# WheeStatX-7.net
KiCad netlist of a schematic drawn in EAGLE
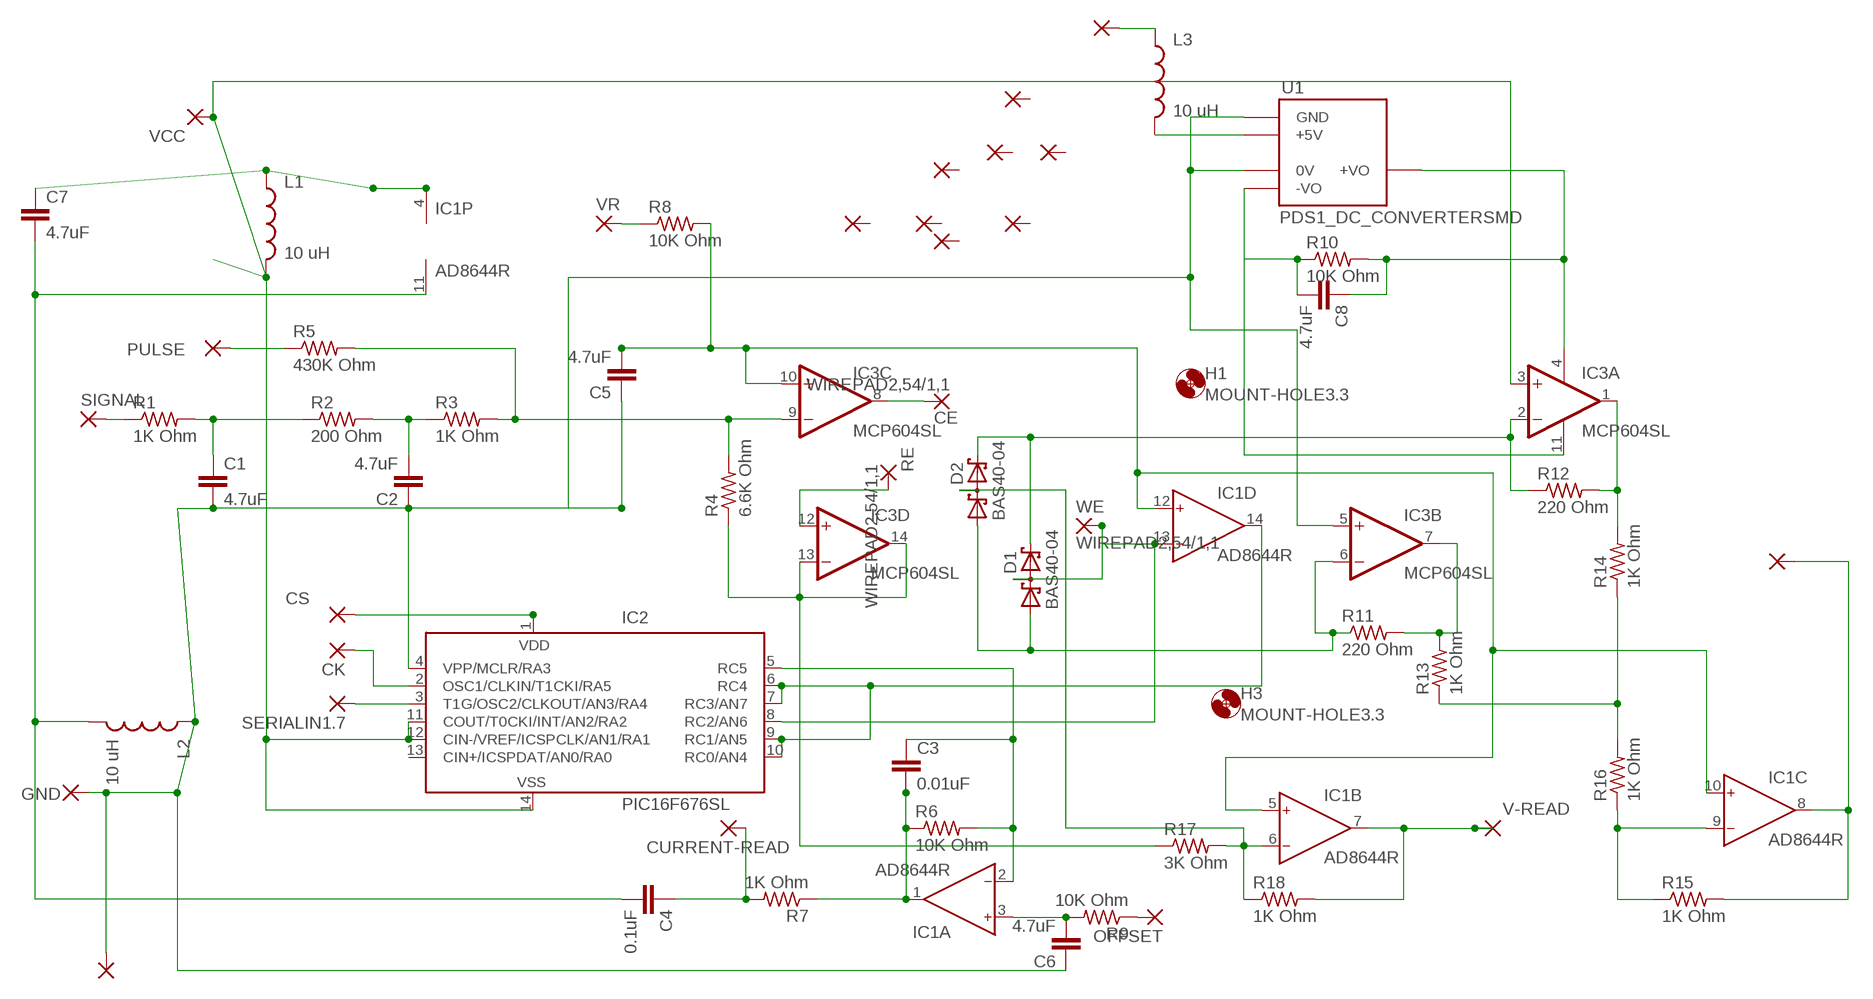
[diagram p0: schematic, sheet 1]

(export (version "E")
  (design (tool "Eeschema 10.0.6"))
  (components
    (comp (ref "1")
      (value "1,6/0,9")
      (footprint "eagle-import:1,6_0,9")
      (libsource (lib "eagle-import") (part "1,6/0,9"))
    )
    (comp (ref "1.1")
      (value "1,6/0,9")
      (footprint "eagle-import:1,6_0,9")
      (libsource (lib "eagle-import") (part "1,6/0,9"))
    )
    (comp (ref "1.4")
      (value "1,6/0,9")
      (footprint "eagle-import:1,6_0,9")
      (libsource (lib "eagle-import") (part "1,6/0,9"))
    )
    (comp (ref "2")
      (value "1,6/0,9")
      (footprint "eagle-import:1,6_0,9")
      (libsource (lib "eagle-import") (part "1,6/0,9"))
    )
    (comp (ref "3")
      (value "1,6/0,9")
      (footprint "eagle-import:1,6_0,9")
      (libsource (lib "eagle-import") (part "1,6/0,9"))
    )
    (comp (ref "4")
      (value "1,6/0,9")
      (footprint "eagle-import:1,6_0,9")
      (libsource (lib "eagle-import") (part "1,6/0,9"))
    )
    (comp (ref "5")
      (value "1,6/0,9")
      (footprint "eagle-import:1,6_0,9")
      (libsource (lib "eagle-import") (part "1,6/0,9"))
    )
    (comp (ref "6")
      (value "1,6/0,9")
      (footprint "eagle-import:1,6_0,9")
      (libsource (lib "eagle-import") (part "1,6/0,9"))
    )
    (comp (ref "7")
      (value "1,6/0,9")
      (footprint "eagle-import:1,6_0,9")
      (libsource (lib "eagle-import") (part "1,6/0,9"))
    )
    (comp (ref "9")
      (value "1,6/0,9")
      (footprint "eagle-import:1,6_0,9")
      (libsource (lib "eagle-import") (part "1,6/0,9"))
    )
    (comp (ref "10")
      (value "1,6/0,9")
      (footprint "eagle-import:1,6_0,9")
      (libsource (lib "eagle-import") (part "1,6/0,9"))
    )
    (comp (ref "C1")
      (value "4.7uF")
      (footprint "eagle-import:C0603")
      (libsource (lib "eagle-import") (part "resistor_C-EUC0603"))
    )
    (comp (ref "C2")
      (value "4.7uF")
      (footprint "eagle-import:C0603")
      (libsource (lib "eagle-import") (part "resistor_C-EUC0603"))
    )
    (comp (ref "C3")
      (value "0.01uF")
      (footprint "eagle-import:C0603")
      (libsource (lib "eagle-import") (part "resistor_C-EUC0603"))
    )
    (comp (ref "C4")
      (value "0.1uF")
      (footprint "eagle-import:C0603")
      (libsource (lib "eagle-import") (part "resistor_C-EUC0603"))
    )
    (comp (ref "C5")
      (value "4.7uF")
      (footprint "eagle-import:C0603")
      (libsource (lib "eagle-import") (part "resistor_C-EUC0603"))
    )
    (comp (ref "C6")
      (value "4.7uF")
      (footprint "eagle-import:C0603")
      (libsource (lib "eagle-import") (part "resistor_C-EUC0603"))
    )
    (comp (ref "C7")
      (value "4.7uF")
      (footprint "eagle-import:C0603@1")
      (libsource (lib "eagle-import") (part "C-EUC0603"))
    )
    (comp (ref "C8")
      (value "4.7uF")
      (footprint "eagle-import:C0603")
      (libsource (lib "eagle-import") (part "resistor_C-EUC0603"))
    )
    (comp (ref "CE")
      (value "WIREPAD2,54/1,1")
      (footprint "eagle-import:2,54_1,1")
      (libsource (lib "eagle-import") (part "WIREPAD2,54/1,1"))
    )
    (comp (ref "CK")
      (value "1,6/0,9")
      (footprint "eagle-import:1,6_0,9")
      (libsource (lib "eagle-import") (part "1,6/0,9"))
    )
    (comp (ref "CS")
      (value "1,6/0,9")
      (footprint "eagle-import:1,6_0,9")
      (libsource (lib "eagle-import") (part "1,6/0,9"))
    )
    (comp (ref "CURRENT-READ")
      (value "1,6/0,9")
      (footprint "eagle-import:1,6_0,9")
      (libsource (lib "eagle-import") (part "1,6/0,9"))
    )
    (comp (ref "D1")
      (value "BAS40-04")
      (footprint "eagle-import:SOT23")
      (libsource (lib "eagle-import") (part "BAS40-04"))
    )
    (comp (ref "D2")
      (value "BAS40-04")
      (footprint "eagle-import:SOT23")
      (libsource (lib "eagle-import") (part "BAS40-04"))
    )
    (comp (ref "GND")
      (value "1,6/0,9")
      (footprint "eagle-import:1,6_0,9")
      (libsource (lib "eagle-import") (part "1,6/0,9"))
    )
    (comp (ref "H1")
      (value "MOUNT-HOLE3.3")
      (footprint "eagle-import:3,3")
      (libsource (lib "eagle-import") (part "MOUNT-HOLE3.3"))
    )
    (comp (ref "H3")
      (value "MOUNT-HOLE3.3")
      (footprint "eagle-import:3,3")
      (libsource (lib "eagle-import") (part "MOUNT-HOLE3.3"))
    )
    (comp (ref "IC1")
      (value "AD8644R")
      (footprint "eagle-import:SO14")
      (fields (field (name "MF") "ALTERA CORPORATION") (field (name "MPN") "AD8644ARZ"))
      (libsource (lib "eagle-import") (part "AD8644R"))
    )
    (comp (ref "IC2")
      (value "PIC16F676SL")
      (footprint "eagle-import:SO-14")
      (fields (field (name "MF") "MICROCHIP") (field (name "MPN") "PIC16F676-I/SL"))
      (libsource (lib "eagle-import") (part "PIC16F676SL"))
    )
    (comp (ref "IC3")
      (value "MCP604SL")
      (footprint "eagle-import:SO14")
      (libsource (lib "eagle-import") (part "MCP604SL"))
    )
    (comp (ref "L1")
      (value "10 uH")
      (footprint "eagle-import:0603")
      (libsource (lib "eagle-import") (part "INDUCTOR0603"))
    )
    (comp (ref "L2")
      (value "10 uH")
      (footprint "eagle-import:0603")
      (libsource (lib "eagle-import") (part "INDUCTOR0603"))
    )
    (comp (ref "L3")
      (value "10 uH")
      (footprint "eagle-import:0603")
      (libsource (lib "eagle-import") (part "INDUCTOR0603"))
    )
    (comp (ref "OFFSET")
      (value "1,6/0,9")
      (footprint "eagle-import:1,6_0,9")
      (libsource (lib "eagle-import") (part "1,6/0,9"))
    )
    (comp (ref "PULSE")
      (value "1,6/0,9")
      (footprint "eagle-import:1,6_0,9")
      (libsource (lib "eagle-import") (part "1,6/0,9"))
    )
    (comp (ref "R1")
      (value "1K Ohm")
      (footprint "eagle-import:R0603")
      (libsource (lib "eagle-import") (part "R-US_R0603"))
    )
    (comp (ref "R2")
      (value "200 Ohm")
      (footprint "eagle-import:R0603")
      (libsource (lib "eagle-import") (part "R-US_R0603"))
    )
    (comp (ref "R3")
      (value "1K Ohm")
      (footprint "eagle-import:R0603")
      (libsource (lib "eagle-import") (part "R-US_R0603"))
    )
    (comp (ref "R4")
      (value "6.6K Ohm")
      (footprint "eagle-import:R0603")
      (libsource (lib "eagle-import") (part "R-US_R0603"))
    )
    (comp (ref "R5")
      (value "430K Ohm")
      (footprint "eagle-import:R0603")
      (libsource (lib "eagle-import") (part "R-US_R0603"))
    )
    (comp (ref "R6")
      (value "10K Ohm")
      (footprint "eagle-import:R0603")
      (libsource (lib "eagle-import") (part "R-US_R0603"))
    )
    (comp (ref "R7")
      (value "1K Ohm")
      (footprint "eagle-import:R0603")
      (libsource (lib "eagle-import") (part "R-US_R0603"))
    )
    (comp (ref "R8")
      (value "10K Ohm")
      (footprint "eagle-import:R0603")
      (libsource (lib "eagle-import") (part "R-US_R0603"))
    )
    (comp (ref "R9")
      (value "10K Ohm")
      (footprint "eagle-import:R0603")
      (libsource (lib "eagle-import") (part "R-US_R0603"))
    )
    (comp (ref "R10")
      (value "10K Ohm")
      (footprint "eagle-import:R0603")
      (libsource (lib "eagle-import") (part "R-US_R0603"))
    )
    (comp (ref "R11")
      (value "220 Ohm")
      (footprint "eagle-import:R0603")
      (libsource (lib "eagle-import") (part "R-US_R0603"))
    )
    (comp (ref "R12")
      (value "220 Ohm")
      (footprint "eagle-import:R0603")
      (libsource (lib "eagle-import") (part "R-US_R0603"))
    )
    (comp (ref "R13")
      (value "1K Ohm")
      (footprint "eagle-import:R0603")
      (libsource (lib "eagle-import") (part "R-US_R0603"))
    )
    (comp (ref "R14")
      (value "1K Ohm")
      (footprint "eagle-import:R0603")
      (libsource (lib "eagle-import") (part "R-US_R0603"))
    )
    (comp (ref "R15")
      (value "1K Ohm")
      (footprint "eagle-import:R0603")
      (libsource (lib "eagle-import") (part "R-US_R0603"))
    )
    (comp (ref "R16")
      (value "1K Ohm")
      (footprint "eagle-import:R0603")
      (libsource (lib "eagle-import") (part "R-US_R0603"))
    )
    (comp (ref "R17")
      (value "3K Ohm")
      (footprint "eagle-import:R0603")
      (libsource (lib "eagle-import") (part "R-US_R0603"))
    )
    (comp (ref "R18")
      (value "1K Ohm")
      (footprint "eagle-import:R0603")
      (libsource (lib "eagle-import") (part "R-US_R0603"))
    )
    (comp (ref "RE")
      (value "WIREPAD2,54/1,1")
      (footprint "eagle-import:2,54_1,1")
      (libsource (lib "eagle-import") (part "WIREPAD2,54/1,1"))
    )
    (comp (ref "SERIALIN1.7")
      (value "1,6/0,9")
      (footprint "eagle-import:1,6_0,9")
      (libsource (lib "eagle-import") (part "1,6/0,9"))
    )
    (comp (ref "SIGNAL")
      (value "1,6/0,9")
      (footprint "eagle-import:1,6_0,9")
      (libsource (lib "eagle-import") (part "1,6/0,9"))
    )
    (comp (ref "U1")
      (value "PDS1_DC_CONVERTERSMD")
      (footprint "eagle-import:PDS1")
      (libsource (lib "eagle-import") (part "PDS1_DC_CONVERTERSMD"))
    )
    (comp (ref "V-READ")
      (value "1,6/0,9")
      (footprint "eagle-import:1,6_0,9")
      (libsource (lib "eagle-import") (part "1,6/0,9"))
    )
    (comp (ref "VCC")
      (value "1,6/0,9")
      (footprint "eagle-import:1,6_0,9")
      (libsource (lib "eagle-import") (part "1,6/0,9"))
    )
    (comp (ref "VR")
      (value "1,6/0,9")
      (footprint "eagle-import:1,6_0,9")
      (libsource (lib "eagle-import") (part "1,6/0,9"))
    )
    (comp (ref "WE")
      (value "WIREPAD2,54/1,1")
      (footprint "eagle-import:2,54_1,1")
      (libsource (lib "eagle-import") (part "WIREPAD2,54/1,1"))
    )
  )
  (nets
    (net (code "1") (name "Net-(1.1-P)") (class "Default")
      (node (ref "1.1") (pin "1") (pinfunction "P_1") (pintype "passive"))
      (node (ref "C1") (pin "2") (pinfunction "2_2") (pintype "passive"))
      (node (ref "C2") (pin "1") (pinfunction "1_1") (pintype "passive"))
      (node (ref "C5") (pin "1") (pinfunction "1_1") (pintype "passive"))
      (node (ref "C6") (pin "1") (pinfunction "1_1") (pintype "passive"))
      (node (ref "GND") (pin "1") (pinfunction "P_1") (pintype "passive"))
      (node (ref "IC2") (pin "4") (pinfunction "VPP/MCLR/RA3_4") (pintype "input"))
      (node (ref "IC3") (pin "5") (pinfunction "+IN_5") (pintype "input"))
      (node (ref "L2") (pin "1") (pinfunction "1_1") (pintype "passive"))
      (node (ref "U1") (pin "1") (pinfunction "GND_1") (pintype "power_in"))
      (node (ref "U1") (pin "4") (pinfunction "0V_4") (pintype "power_in"))
    )
    (net (code "2") (name "Net-(1.4-P)") (class "Default")
      (node (ref "1.4") (pin "1") (pinfunction "P_1") (pintype "passive"))
      (node (ref "IC1") (pin "8") (pinfunction "OUT_8") (pintype "output"))
      (node (ref "R15") (pin "2") (pinfunction "2_2") (pintype "passive"))
    )
    (net (code "3") (name "Net-(9-P)") (class "Default")
      (node (ref "9") (pin "1") (pinfunction "P_1") (pintype "passive"))
      (node (ref "L3") (pin "1") (pinfunction "1_1") (pintype "passive"))
    )
    (net (code "4") (name "Net-(C1-Pad1)") (class "Default")
      (node (ref "C1") (pin "1") (pinfunction "1_1") (pintype "passive"))
      (node (ref "R1") (pin "2") (pinfunction "2_2") (pintype "passive"))
      (node (ref "R2") (pin "1") (pinfunction "1_1") (pintype "passive"))
    )
    (net (code "5") (name "Net-(C2-Pad2)") (class "Default")
      (node (ref "C2") (pin "2") (pinfunction "2_2") (pintype "passive"))
      (node (ref "R2") (pin "2") (pinfunction "2_2") (pintype "passive"))
      (node (ref "R3") (pin "1") (pinfunction "1_1") (pintype "passive"))
    )
    (net (code "6") (name "Net-(CE-P)") (class "Default")
      (node (ref "CE") (pin "1") (pinfunction "P_1") (pintype "passive"))
      (node (ref "IC3") (pin "8") (pinfunction "OUT_8") (pintype "output"))
    )
    (net (code "7") (name "Net-(CK-P)") (class "Default")
      (node (ref "CK") (pin "1") (pinfunction "P_1") (pintype "passive"))
      (node (ref "IC2") (pin "2") (pinfunction "OSC1/CLKIN/T1CKI/RA5_2") (pintype "bidirectional"))
    )
    (net (code "8") (name "Net-(CS-P)") (class "Default")
      (node (ref "CS") (pin "1") (pinfunction "P_1") (pintype "passive"))
      (node (ref "IC2") (pin "1") (pinfunction "VDD_1") (pintype "power_in"))
    )
    (net (code "9") (name "Net-(CURRENT-READ-P)") (class "Default")
      (node (ref "C4") (pin "1") (pinfunction "1_1") (pintype "passive"))
      (node (ref "CURRENT-READ") (pin "1") (pinfunction "P_1") (pintype "passive"))
      (node (ref "R7") (pin "2") (pinfunction "2_2") (pintype "passive"))
    )
    (net (code "10") (name "Net-(D1-A1)") (class "Default")
      (node (ref "D1") (pin "1") (pinfunction "A1_1") (pintype "passive"))
      (node (ref "D2") (pin "1") (pinfunction "A1_1") (pintype "passive"))
      (node (ref "IC3") (pin "6") (pinfunction "-IN_6") (pintype "input"))
      (node (ref "R11") (pin "1") (pinfunction "1_1") (pintype "passive"))
    )
    (net (code "11") (name "Net-(D1-C1A2)") (class "Default")
      (node (ref "D1") (pin "3") (pinfunction "C1A2_3") (pintype "passive"))
      (node (ref "IC1") (pin "13") (pinfunction "IN-_13") (pintype "input"))
      (node (ref "IC2") (pin "8") (pinfunction "RC2/AN6_8") (pintype "bidirectional"))
      (node (ref "WE") (pin "1") (pinfunction "P_1") (pintype "passive"))
    )
    (net (code "12") (name "Net-(D1-C2)") (class "Default")
      (node (ref "D1") (pin "2") (pinfunction "C2_2") (pintype "passive"))
      (node (ref "D2") (pin "2") (pinfunction "C2_2") (pintype "passive"))
      (node (ref "IC3") (pin "2") (pinfunction "-IN_2") (pintype "input"))
      (node (ref "R12") (pin "1") (pinfunction "1_1") (pintype "passive"))
    )
    (net (code "13") (name "Net-(D2-C1A2)") (class "Default")
      (node (ref "D2") (pin "3") (pinfunction "C1A2_3") (pintype "passive"))
      (node (ref "IC1") (pin "6") (pinfunction "IN-_6") (pintype "input"))
      (node (ref "R17") (pin "2") (pinfunction "2_2") (pintype "passive"))
      (node (ref "R18") (pin "1") (pinfunction "1_1") (pintype "passive"))
    )
    (net (code "14") (name "Net-(IC1A-IN+)") (class "Default")
      (node (ref "C6") (pin "2") (pinfunction "2_2") (pintype "passive"))
      (node (ref "IC1") (pin "3") (pinfunction "IN+_3") (pintype "input"))
      (node (ref "R9") (pin "2") (pinfunction "2_2") (pintype "passive"))
    )
    (net (code "15") (name "Net-(IC1A-IN-)") (class "Default")
      (node (ref "C3") (pin "1") (pinfunction "1_1") (pintype "passive"))
      (node (ref "IC1") (pin "2") (pinfunction "IN-_2") (pintype "input"))
      (node (ref "IC2") (pin "5") (pinfunction "RC5_5") (pintype "bidirectional"))
      (node (ref "R6") (pin "2") (pinfunction "2_2") (pintype "passive"))
    )
    (net (code "16") (name "Net-(IC1A-OUT)") (class "Default")
      (node (ref "C3") (pin "2") (pinfunction "2_2") (pintype "passive"))
      (node (ref "IC1") (pin "1") (pinfunction "OUT_1") (pintype "output"))
      (node (ref "R6") (pin "1") (pinfunction "1_1") (pintype "passive"))
      (node (ref "R7") (pin "1") (pinfunction "1_1") (pintype "passive"))
    )
    (net (code "17") (name "Net-(IC1B-IN+)") (class "Default")
      (node (ref "C5") (pin "2") (pinfunction "2_2") (pintype "passive"))
      (node (ref "IC1") (pin "10") (pinfunction "IN+_10") (pintype "input"))
      (node (ref "IC1") (pin "12") (pinfunction "IN+_12") (pintype "input"))
      (node (ref "IC1") (pin "5") (pinfunction "IN+_5") (pintype "input"))
      (node (ref "IC3") (pin "10") (pinfunction "+IN_10") (pintype "input"))
      (node (ref "R8") (pin "2") (pinfunction "2_2") (pintype "passive"))
    )
    (net (code "18") (name "Net-(IC1B-OUT)") (class "Default")
      (node (ref "IC1") (pin "7") (pinfunction "OUT_7") (pintype "output"))
      (node (ref "R18") (pin "2") (pinfunction "2_2") (pintype "passive"))
      (node (ref "V-READ") (pin "1") (pinfunction "P_1") (pintype "passive"))
    )
    (net (code "19") (name "Net-(IC1C-IN-)") (class "Default")
      (node (ref "IC1") (pin "9") (pinfunction "IN-_9") (pintype "input"))
      (node (ref "R15") (pin "1") (pinfunction "1_1") (pintype "passive"))
      (node (ref "R16") (pin "1") (pinfunction "1_1") (pintype "passive"))
    )
    (net (code "20") (name "Net-(IC1D-OUT)") (class "Default")
      (node (ref "IC1") (pin "14") (pinfunction "OUT_14") (pintype "output"))
      (node (ref "IC2") (pin "10") (pinfunction "RC0/AN4_10") (pintype "bidirectional"))
      (node (ref "IC2") (pin "6") (pinfunction "RC4_6") (pintype "bidirectional"))
      (node (ref "IC2") (pin "7") (pinfunction "RC3/AN7_7") (pintype "bidirectional"))
      (node (ref "IC2") (pin "9") (pinfunction "RC1/AN5_9") (pintype "bidirectional"))
    )
    (net (code "21") (name "Net-(IC1E-V+)") (class "Default")
      (node (ref "C7") (pin "1") (pinfunction "1_1") (pintype "passive"))
      (node (ref "IC1") (pin "4") (pinfunction "V+_4") (pintype "power_in"))
      (node (ref "L1") (pin "1") (pinfunction "1_1") (pintype "passive"))
    )
    (net (code "22") (name "Net-(IC1E-V-)") (class "Default")
      (node (ref "C4") (pin "2") (pinfunction "2_2") (pintype "passive"))
      (node (ref "C7") (pin "2") (pinfunction "2_2") (pintype "passive"))
      (node (ref "IC1") (pin "11") (pinfunction "V-_11") (pintype "power_in"))
      (node (ref "L2") (pin "2") (pinfunction "2_2") (pintype "passive"))
    )
    (net (code "23") (name "Net-(IC2-CIN-{slash}VREF{slash}ICSPCLK{slash}AN1{slash}RA1)") (class "Default")
      (node (ref "IC2") (pin "11") (pinfunction "COUT/T0CKI/INT/AN2/RA2_11") (pintype "bidirectional"))
      (node (ref "IC2") (pin "12") (pinfunction "CIN-/VREF/ICSPCLK/AN1/RA1_12") (pintype "bidirectional"))
      (node (ref "IC2") (pin "14") (pinfunction "VSS_14") (pintype "power_in"))
      (node (ref "IC3") (pin "3") (pinfunction "+IN_3") (pintype "input"))
      (node (ref "L1") (pin "2") (pinfunction "2_2") (pintype "passive"))
      (node (ref "VCC") (pin "1") (pinfunction "P_1") (pintype "passive"))
    )
    (net (code "24") (name "Net-(IC2-T1G{slash}OSC2{slash}CLKOUT{slash}AN3{slash}RA4)") (class "Default")
      (node (ref "IC2") (pin "3") (pinfunction "T1G/OSC2/CLKOUT/AN3/RA4_3") (pintype "bidirectional"))
      (node (ref "SERIALIN1.7") (pin "1") (pinfunction "P_1") (pintype "passive"))
    )
    (net (code "25") (name "Net-(IC3A-OUT)") (class "Default")
      (node (ref "IC3") (pin "1") (pinfunction "OUT_1") (pintype "output"))
      (node (ref "R12") (pin "2") (pinfunction "2_2") (pintype "passive"))
      (node (ref "R14") (pin "2") (pinfunction "2_2") (pintype "passive"))
    )
    (net (code "26") (name "Net-(IC3B-OUT)") (class "Default")
      (node (ref "IC3") (pin "7") (pinfunction "OUT_7") (pintype "output"))
      (node (ref "R11") (pin "2") (pinfunction "2_2") (pintype "passive"))
      (node (ref "R13") (pin "2") (pinfunction "2_2") (pintype "passive"))
    )
    (net (code "27") (name "Net-(IC3C--IN)") (class "Default")
      (node (ref "IC3") (pin "9") (pinfunction "-IN_9") (pintype "input"))
      (node (ref "R3") (pin "2") (pinfunction "2_2") (pintype "passive"))
      (node (ref "R4") (pin "2") (pinfunction "2_2") (pintype "passive"))
      (node (ref "R5") (pin "2") (pinfunction "2_2") (pintype "passive"))
    )
    (net (code "28") (name "Net-(IC3D-+IN)") (class "Default")
      (node (ref "IC3") (pin "12") (pinfunction "+IN_12") (pintype "input"))
      (node (ref "RE") (pin "1") (pinfunction "P_1") (pintype "passive"))
    )
    (net (code "29") (name "Net-(IC3D--IN)") (class "Default")
      (node (ref "IC3") (pin "13") (pinfunction "-IN_13") (pintype "input"))
      (node (ref "IC3") (pin "14") (pinfunction "OUT_14") (pintype "output"))
      (node (ref "R17") (pin "1") (pinfunction "1_1") (pintype "passive"))
      (node (ref "R4") (pin "1") (pinfunction "1_1") (pintype "passive"))
    )
    (net (code "30") (name "Net-(IC3E-V+)") (class "Default")
      (node (ref "C8") (pin "1") (pinfunction "1_1") (pintype "passive"))
      (node (ref "IC3") (pin "4") (pinfunction "V+_4") (pintype "power_in"))
      (node (ref "R10") (pin "2") (pinfunction "2_2") (pintype "passive"))
      (node (ref "U1") (pin "7") (pinfunction "+VO_7") (pintype "power_in"))
    )
    (net (code "31") (name "Net-(IC3E-V-)") (class "Default")
      (node (ref "C8") (pin "2") (pinfunction "2_2") (pintype "passive"))
      (node (ref "IC3") (pin "11") (pinfunction "V-_11") (pintype "power_in"))
      (node (ref "R10") (pin "1") (pinfunction "1_1") (pintype "passive"))
      (node (ref "U1") (pin "5") (pinfunction "-VO_5") (pintype "power_in"))
    )
    (net (code "32") (name "Net-(OFFSET-P)") (class "Default")
      (node (ref "OFFSET") (pin "1") (pinfunction "P_1") (pintype "passive"))
      (node (ref "R9") (pin "1") (pinfunction "1_1") (pintype "passive"))
    )
    (net (code "33") (name "Net-(PULSE-P)") (class "Default")
      (node (ref "PULSE") (pin "1") (pinfunction "P_1") (pintype "passive"))
      (node (ref "R5") (pin "1") (pinfunction "1_1") (pintype "passive"))
    )
    (net (code "34") (name "Net-(R13-Pad1)") (class "Default")
      (node (ref "R13") (pin "1") (pinfunction "1_1") (pintype "passive"))
      (node (ref "R14") (pin "1") (pinfunction "1_1") (pintype "passive"))
      (node (ref "R16") (pin "2") (pinfunction "2_2") (pintype "passive"))
    )
    (net (code "35") (name "Net-(SIGNAL-P)") (class "Default")
      (node (ref "R1") (pin "1") (pinfunction "1_1") (pintype "passive"))
      (node (ref "SIGNAL") (pin "1") (pinfunction "P_1") (pintype "passive"))
    )
    (net (code "36") (name "Net-(U1-+5V)") (class "Default")
      (node (ref "L3") (pin "2") (pinfunction "2_2") (pintype "passive"))
      (node (ref "U1") (pin "2") (pinfunction "+5V_2") (pintype "power_in"))
    )
    (net (code "37") (name "Net-(VR-P)") (class "Default")
      (node (ref "R8") (pin "1") (pinfunction "1_1") (pintype "passive"))
      (node (ref "VR") (pin "1") (pinfunction "P_1") (pintype "passive"))
    )
    (net (code "38") (name "unconnected-(1-P-Pad1)") (class "Default")
      (node (ref "1") (pin "1") (pinfunction "P_1") (pintype "passive"))
    )
    (net (code "39") (name "unconnected-(2-P-Pad1)") (class "Default")
      (node (ref "2") (pin "1") (pinfunction "P_1") (pintype "passive"))
    )
    (net (code "40") (name "unconnected-(3-P-Pad1)") (class "Default")
      (node (ref "3") (pin "1") (pinfunction "P_1") (pintype "passive"))
    )
    (net (code "41") (name "unconnected-(4-P-Pad1)") (class "Default")
      (node (ref "4") (pin "1") (pinfunction "P_1") (pintype "passive"))
    )
    (net (code "42") (name "unconnected-(5-P-Pad1)") (class "Default")
      (node (ref "5") (pin "1") (pinfunction "P_1") (pintype "passive"))
    )
    (net (code "43") (name "unconnected-(6-P-Pad1)") (class "Default")
      (node (ref "6") (pin "1") (pinfunction "P_1") (pintype "passive"))
    )
    (net (code "44") (name "unconnected-(7-P-Pad1)") (class "Default")
      (node (ref "7") (pin "1") (pinfunction "P_1") (pintype "passive"))
    )
    (net (code "45") (name "unconnected-(10-P-Pad1)") (class "Default")
      (node (ref "10") (pin "1") (pinfunction "P_1") (pintype "passive"))
    )
    (net (code "46") (name "unconnected-(IC2-CIN+{slash}ICSPDAT{slash}AN0{slash}RA0-Pad13)") (class "Default")
      (node (ref "IC2") (pin "13") (pinfunction "CIN+/ICSPDAT/AN0/RA0_13") (pintype "bidirectional"))
    )
  )
)
